# BlockSchematic.net
KiCad netlist of a schematic drawn in Altium Designer
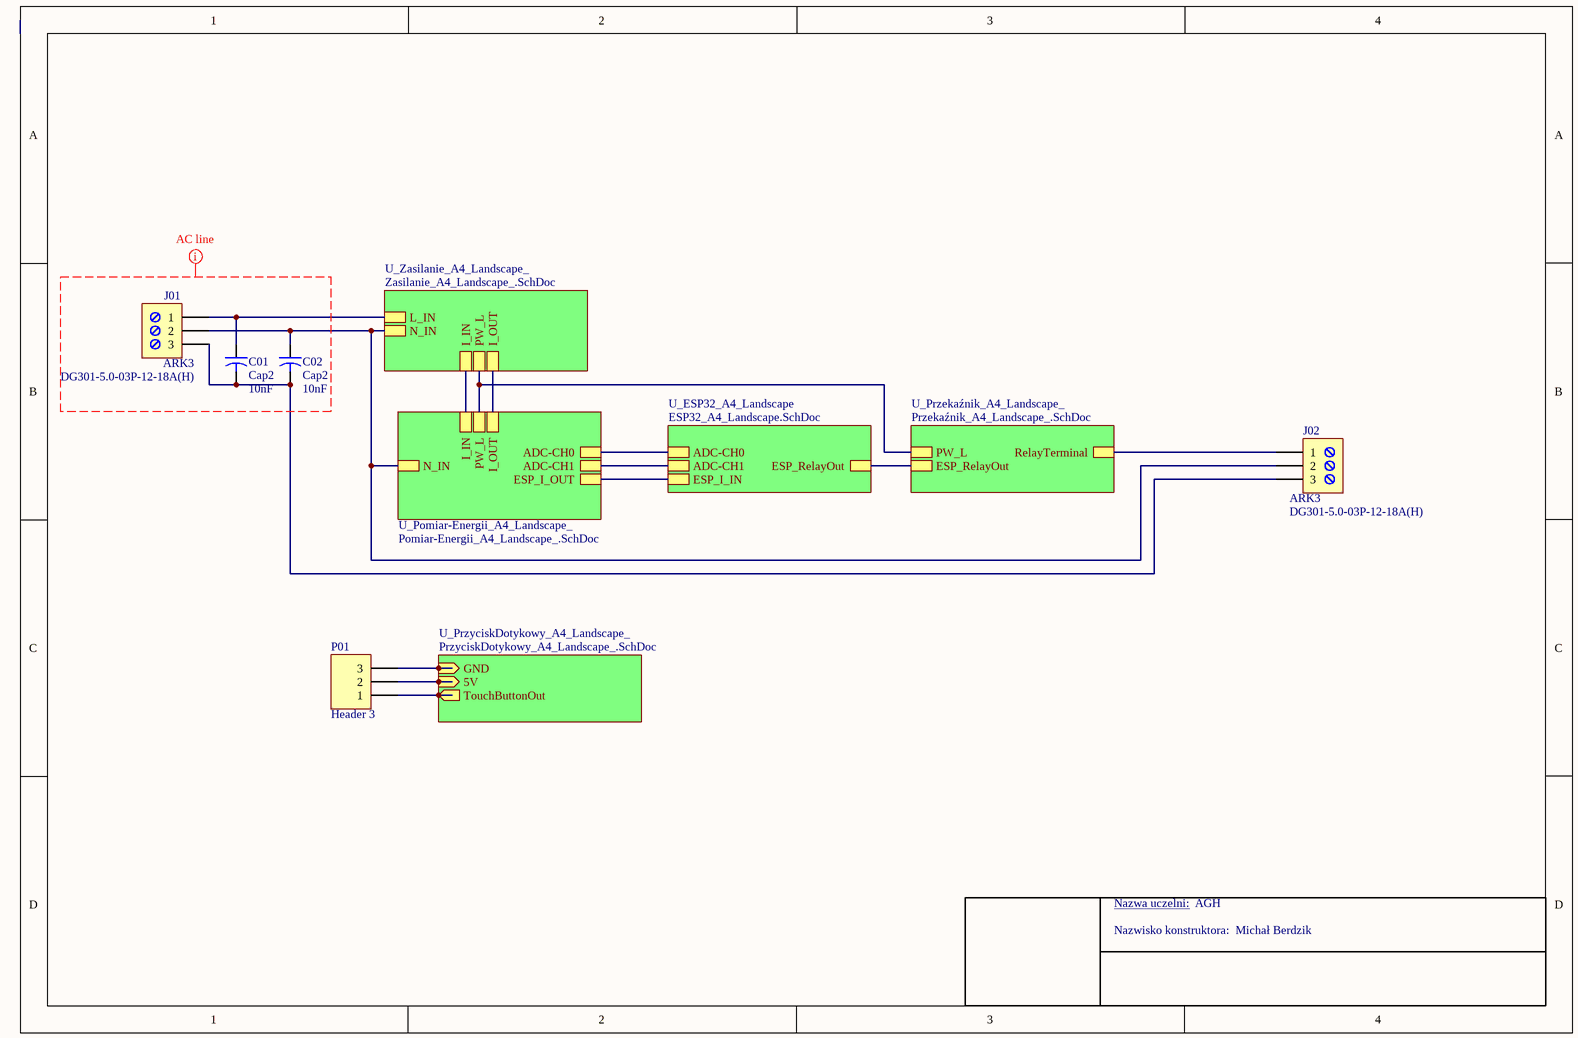
[diagram p0: BlockSchematic.SchDoc]

(export (version "E")
  (design (tool "Eeschema 10.0.6"))
  (components
    (comp (ref "C01")
      (value "Cap2")
      (footprint "CAPR5-4X5")
      (description "Capacitor")
      (fields (field (name "ALTIUM_VALUE") "10nF") (field (name "PUBLISHER") "Altium Limited"))
      (libsource (lib "Miscellaneous Devices") (part "Cap2"))
    )
    (comp (ref "C02")
      (value "Cap2")
      (footprint "CAPR5-4X5")
      (description "Capacitor")
      (fields (field (name "ALTIUM_VALUE") "10nF") (field (name "PUBLISHER") "Altium Limited"))
      (libsource (lib "Miscellaneous Devices") (part "Cap2"))
    )
    (comp (ref "J01")
      (value "DG301-5.0-03P-12-18A(H)")
      (footprint "J_ARK3")
      (description "ARK Screw terminal, 3-Pin")
      (fields
        (field (name "SCH_FOOTPRINT") "ARK3")
        (field (name "PART NUMBER") "J_TB-5.0-P-3P")
        (field (name "MANUFACTURER") "DEGSON ELECTRONICS")
      )
      (libsource (lib "Library") (part "J_ARK3"))
    )
    (comp (ref "J02")
      (value "DG301-5.0-03P-12-18A(H)")
      (footprint "J_ARK3")
      (description "ARK Screw terminal, 3-Pin")
      (fields
        (field (name "SCH_FOOTPRINT") "ARK3")
        (field (name "PART NUMBER") "J_TB-5.0-P-3P")
        (field (name "MANUFACTURER") "DEGSON ELECTRONICS")
      )
      (libsource (lib "") (part "J_ARK3_1"))
    )
    (comp (ref "P01")
      (value "Header 3")
      (footprint "HDR1X3")
      (description "Header, 3-Pin")
      (fields (field (name "PUBLISHER") "Altium Limited"))
      (libsource (lib "Miscellaneous Connectors") (part "Header 3"))
    )
  )
  (nets
    (net (code "1") (name "/5V") (class "Default")
      (node (ref "P01") (pin "2") (pinfunction "2_2") (pintype "passive"))
    )
    (net (code "6") (name "/GND") (class "Default")
      (node (ref "P01") (pin "3") (pinfunction "3_3") (pintype "passive"))
    )
    (net (code "9") (name "/L_IN") (class "Default")
      (node (ref "C01") (pin "1") (pinfunction "1_1") (pintype "passive"))
      (node (ref "J01") (pin "1") (pinfunction "1_1") (pintype "passive"))
    )
    (net (code "10") (name "/N_IN") (class "Default")
      (node (ref "C02") (pin "1") (pinfunction "1_1") (pintype "passive"))
      (node (ref "J01") (pin "2") (pinfunction "2_2") (pintype "passive"))
      (node (ref "J02") (pin "2") (pinfunction "2_2") (pintype "passive"))
    )
    (net (code "12") (name "/RelayTerminal") (class "Default")
      (node (ref "J02") (pin "1") (pinfunction "1_1") (pintype "passive"))
    )
    (net (code "13") (name "/TouchButtonOut") (class "Default")
      (node (ref "P01") (pin "1") (pinfunction "1_1") (pintype "passive"))
    )
    (net (code "14") (name "Net-(C01-Pad2)") (class "Default")
      (node (ref "C01") (pin "2") (pinfunction "2_2") (pintype "passive"))
      (node (ref "C02") (pin "2") (pinfunction "2_2") (pintype "passive"))
      (node (ref "J01") (pin "3") (pinfunction "3_3") (pintype "passive"))
      (node (ref "J02") (pin "3") (pinfunction "3_3") (pintype "passive"))
    )
  )
)
